# PSU.net
KiCad netlist of a schematic drawn in Altium Designer
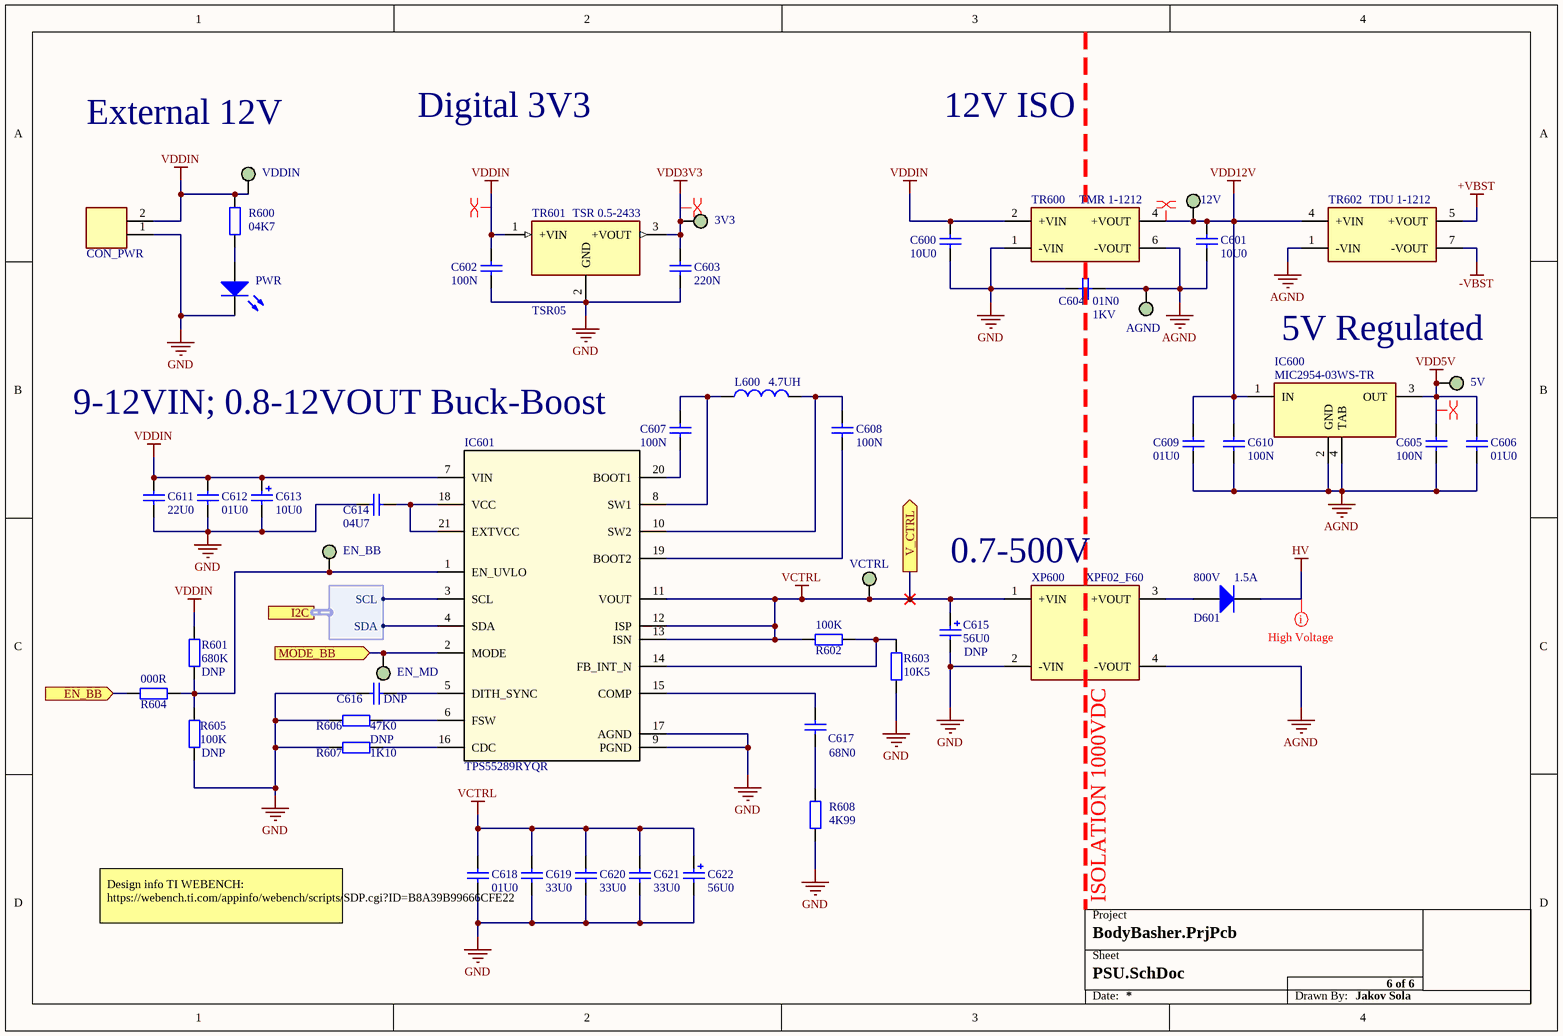
[diagram p0: PSU.SchDoc]

(export (version "E")
  (design (tool "Eeschema 10.0.6"))
  (components
    (comp (ref "3V3") (value "TP") (footprint "TP") (libsource (lib "Other_passive") (part "TP")))
    (comp (ref "5V") (value "TP") (footprint "TP") (libsource (lib "Other_passive") (part "TP")))
    (comp (ref "12V") (value "TP") (footprint "TP") (libsource (lib "Other_passive") (part "TP")))
    (comp (ref "AGND") (value "TP") (footprint "TP") (libsource (lib "Other_passive") (part "TP")))
    (comp (ref "C600")
      (value "Cap")
      (footprint "CAPC0603N")
      (fields
        (field (name "VALUE_4C") "10U0")
        (field (name "VOLTAGE") "25V")
        (field (name "TOLERANCE") "0.2")
      )
      (libsource (lib "Capacitors") (part "Cap"))
    )
    (comp (ref "C601")
      (value "Cap")
      (footprint "CAPC0603N")
      (fields
        (field (name "VALUE_4C") "10U0")
        (field (name "VOLTAGE") "25V")
        (field (name "TOLERANCE") "0.2")
      )
      (libsource (lib "Capacitors") (part "Cap"))
    )
    (comp (ref "C602")
      (value "Cap")
      (footprint "CAPC0603N")
      (fields
        (field (name "VALUE_4C") "100N")
        (field (name "VOLTAGE") "25V")
        (field (name "TOLERANCE") "0.1")
      )
      (libsource (lib "Capacitors") (part "Cap"))
    )
    (comp (ref "C603")
      (value "Cap")
      (footprint "CAPC0603N")
      (fields
        (field (name "VALUE_4C") "220N")
        (field (name "VOLTAGE") "10V")
        (field (name "TOLERANCE") "0.1")
      )
      (libsource (lib "Capacitors") (part "Cap"))
    )
    (comp (ref "C604")
      (value "Cap")
      (footprint "CAPC1206N")
      (fields
        (field (name "VALUE_4C") "01N0")
        (field (name "VOLTAGE") "1KV")
        (field (name "TOLERANCE") "0.1")
      )
      (libsource (lib "Capacitors") (part "Cap"))
    )
    (comp (ref "C605")
      (value "Cap")
      (footprint "CAPC0603N")
      (fields
        (field (name "VALUE_4C") "100N")
        (field (name "VOLTAGE") "25V")
        (field (name "TOLERANCE") "0.1")
      )
      (libsource (lib "Capacitors") (part "Cap"))
    )
    (comp (ref "C606")
      (value "Cap")
      (footprint "CAPC0603N")
      (fields
        (field (name "VALUE_4C") "01U0")
        (field (name "VOLTAGE") "16V")
        (field (name "TOLERANCE") "0.1")
      )
      (libsource (lib "Capacitors") (part "Cap"))
    )
    (comp (ref "C607")
      (value "Cap")
      (footprint "CAPC0603N")
      (fields
        (field (name "VALUE_4C") "100N")
        (field (name "VOLTAGE") "25V")
        (field (name "TOLERANCE") "0.1")
      )
      (libsource (lib "Capacitors") (part "Cap"))
    )
    (comp (ref "C608")
      (value "Cap")
      (footprint "CAPC0603N")
      (fields
        (field (name "VALUE_4C") "100N")
        (field (name "VOLTAGE") "25V")
        (field (name "TOLERANCE") "0.1")
      )
      (libsource (lib "Capacitors") (part "Cap"))
    )
    (comp (ref "C609")
      (value "Cap")
      (footprint "CAPC0603N")
      (fields
        (field (name "VALUE_4C") "01U0")
        (field (name "VOLTAGE") "16V")
        (field (name "TOLERANCE") "0.1")
      )
      (libsource (lib "Capacitors") (part "Cap"))
    )
    (comp (ref "C610")
      (value "Cap")
      (footprint "CAPC0603N")
      (fields
        (field (name "VALUE_4C") "100N")
        (field (name "VOLTAGE") "25V")
        (field (name "TOLERANCE") "0.1")
      )
      (libsource (lib "Capacitors") (part "Cap"))
    )
    (comp (ref "C611")
      (value "Cap")
      (footprint "CAPC1206N")
      (fields
        (field (name "VALUE_4C") "22U0")
        (field (name "VOLTAGE") "25V")
        (field (name "TOLERANCE") "0.1")
      )
      (libsource (lib "Capacitors") (part "Cap"))
    )
    (comp (ref "C612")
      (value "Cap")
      (footprint "CAPC0603N")
      (fields
        (field (name "VALUE_4C") "01U0")
        (field (name "VOLTAGE") "25V")
        (field (name "TOLERANCE") "0.1")
      )
      (libsource (lib "Capacitors") (part "Cap"))
    )
    (comp (ref "C613")
      (value "CapPol")
      (footprint "C")
      (fields
        (field (name "VALUE_4C") "10U0")
        (field (name "VOLTAGE") "25V")
        (field (name "TOLERANCE") "0.1")
      )
      (libsource (lib "Capacitors") (part "CapPol"))
    )
    (comp (ref "C614")
      (value "Cap")
      (footprint "CAPC0603N")
      (fields
        (field (name "VALUE_4C") "04U7")
        (field (name "VOLTAGE") "16V")
        (field (name "TOLERANCE") "0.1")
      )
      (libsource (lib "Capacitors") (part "Cap"))
    )
    (comp (ref "C615")
      (value "CapPol")
      (footprint "20SVPF56MX")
      (fields
        (field (name "POPULATE") "DNP")
        (field (name "VALUE_4C") "56U0")
        (field (name "VOLTAGE") "20V")
        (field (name "TOLERANCE") "0.2")
      )
      (libsource (lib "Capacitors") (part "CapPol"))
    )
    (comp (ref "C616")
      (value "Cap")
      (footprint "CAPC0603N")
      (fields (field (name "POPULATE") "DNP") (field (name "VOLTAGE") "25V") (field (name "TOLERANCE") "0.1"))
      (libsource (lib "Capacitors") (part "Cap"))
    )
    (comp (ref "C617")
      (value "Cap")
      (footprint "CAPC0603N")
      (fields
        (field (name "VALUE_4C") "68N0")
        (field (name "VOLTAGE") "10V")
        (field (name "TOLERANCE") "0.1")
      )
      (libsource (lib "Capacitors") (part "Cap"))
    )
    (comp (ref "C618")
      (value "Cap")
      (footprint "CAPC0603N")
      (fields
        (field (name "VALUE_4C") "01U0")
        (field (name "VOLTAGE") "25V")
        (field (name "TOLERANCE") "0.1")
      )
      (libsource (lib "Capacitors") (part "Cap"))
    )
    (comp (ref "C619")
      (value "Cap")
      (footprint "CAPC1206N")
      (fields
        (field (name "VALUE_4C") "33U0")
        (field (name "VOLTAGE") "25V")
        (field (name "TOLERANCE") "0.2")
      )
      (libsource (lib "Capacitors") (part "Cap"))
    )
    (comp (ref "C620")
      (value "Cap")
      (footprint "CAPC1206N")
      (fields
        (field (name "VALUE_4C") "33U0")
        (field (name "VOLTAGE") "25V")
        (field (name "TOLERANCE") "0.2")
      )
      (libsource (lib "Capacitors") (part "Cap"))
    )
    (comp (ref "C621")
      (value "Cap")
      (footprint "CAPC1206N")
      (fields
        (field (name "VALUE_4C") "33U0")
        (field (name "VOLTAGE") "25V")
        (field (name "TOLERANCE") "0.2")
      )
      (libsource (lib "Capacitors") (part "Cap"))
    )
    (comp (ref "C622")
      (value "CapPol")
      (footprint "20SVPF56MX")
      (fields
        (field (name "VALUE_4C") "56U0")
        (field (name "VOLTAGE") "20V")
        (field (name "TOLERANCE") "0.2")
      )
      (libsource (lib "Capacitors") (part "CapPol"))
    )
    (comp (ref "CON_PWR")
      (value "CON_2P")
      (footprint "1711725")
      (libsource (lib "Other_passive") (part "CON_2P"))
    )
    (comp (ref "D601")
      (value "Diode")
      (footprint "DIOSMB")
      (description "Default Diode")
      (fields (field (name "IF") "1.5A") (field (name "VR") "800V"))
      (libsource (lib "Diodes") (part "Diode"))
    )
    (comp (ref "EN_BB") (value "TP") (footprint "TP") (libsource (lib "Other_passive") (part "TP")))
    (comp (ref "EN_MD") (value "TP") (footprint "TP") (libsource (lib "Other_passive") (part "TP")))
    (comp (ref "IC600")
      (value "MIC2954-03WS-TR")
      (footprint "SOT230P700X180-4N")
      (fields (field (name "MANUFCODE") "MIC2954-03WS-TR"))
      (libsource (lib "Integrated_circuits") (part "MIC2954-03WS-TR"))
    )
    (comp (ref "IC601")
      (value "TPS55289RYQR")
      (footprint "RYQ0021A-MFG")
      (fields (field (name "MANUFCODE") "TPS55289RYQR"))
      (libsource (lib "Integrated_circuits") (part "TPS55289RYQR"))
    )
    (comp (ref "L600")
      (value "Inductor")
      (footprint "SRN80404R7Y")
      (fields (field (name "INDUCTANCE") "4.7UH"))
      (libsource (lib "Other_passive") (part "Inductor"))
    )
    (comp (ref "PWR") (value "LED") (footprint "LED0603_GREEN") (libsource (lib "Diodes") (part "LED")))
    (comp (ref "R600")
      (value "Res")
      (footprint "RESC0603N")
      (description "Resistor")
      (fields (field (name "VALUE_4C") "04K7") (field (name "POWER") "0.1W") (field (name "TOLERANCE") "5%"))
      (libsource (lib "Resistors") (part "Res"))
    )
    (comp (ref "R601")
      (value "Res")
      (footprint "RESC0603N")
      (description "Resistor")
      (fields
        (field (name "POPULATE") "DNP")
        (field (name "VALUE_4C") "680K")
        (field (name "POWER") "0.1W")
        (field (name "TOLERANCE") "1%")
      )
      (libsource (lib "Resistors") (part "Res"))
    )
    (comp (ref "R602")
      (value "Res")
      (footprint "RESC0603N")
      (description "Resistor")
      (fields
        (field (name "VALUE_4C") "100K")
        (field (name "POWER") "0.063W")
        (field (name "TOLERANCE") "1%")
      )
      (libsource (lib "") (part "Res_2"))
    )
    (comp (ref "R603")
      (value "Res")
      (footprint "RESC0603N")
      (description "Resistor")
      (fields
        (field (name "VALUE_4C") "10K5")
        (field (name "POWER") "0.063W")
        (field (name "TOLERANCE") "1%")
      )
      (libsource (lib "") (part "Res_3"))
    )
    (comp (ref "R604")
      (value "Res")
      (footprint "RESC0603N")
      (description "Resistor")
      (fields (field (name "VALUE_4C") "000R") (field (name "POWER") "0.1W") (field (name "TOLERANCE") "1%"))
      (libsource (lib "") (part "Res_2"))
    )
    (comp (ref "R605")
      (value "Res")
      (footprint "RESC0603N")
      (description "Resistor")
      (fields
        (field (name "POPULATE") "DNP")
        (field (name "VALUE_4C") "100K")
        (field (name "POWER") "0.063W")
        (field (name "TOLERANCE") "1%")
      )
      (libsource (lib "Resistors") (part "Res"))
    )
    (comp (ref "R606")
      (value "Res")
      (footprint "RESC0603N")
      (description "Resistor")
      (fields (field (name "VALUE_4C") "47K0") (field (name "POWER") "0.1W") (field (name "TOLERANCE") "1%"))
      (libsource (lib "") (part "Res_1"))
    )
    (comp (ref "R607")
      (value "Res")
      (footprint "RESC0603N")
      (description "Resistor")
      (fields
        (field (name "POPULATE") "DNP")
        (field (name "VALUE_4C") "1K10")
        (field (name "POWER") "0.1W")
        (field (name "TOLERANCE") "1%")
      )
      (libsource (lib "") (part "Res_2"))
    )
    (comp (ref "R608")
      (value "Res")
      (footprint "RESC0603N")
      (description "Resistor")
      (fields
        (field (name "VALUE_4C") "4K99")
        (field (name "POWER") "0.063W")
        (field (name "TOLERANCE") "1%")
      )
      (libsource (lib "Resistors") (part "Res"))
    )
    (comp (ref "TR600")
      (value "TMR1")
      (footprint "TMR1")
      (fields (field (name "MANUFCODE") "TMR 1-1212"))
      (libsource (lib "Integrated_circuits") (part "TMR1"))
    )
    (comp (ref "TR601")
      (value "TSR05")
      (footprint "TSR05")
      (fields (field (name "MANUFCODE") "TSR 0.5-2433"))
      (libsource (lib "Integrated_circuits") (part "TSR05"))
    )
    (comp (ref "TR602")
      (value "TDU1")
      (footprint "TDU1")
      (fields (field (name "MANUFCODE") "TDU 1-1212"))
      (libsource (lib "Integrated_circuits") (part "TDU1"))
    )
    (comp (ref "VCTRL") (value "TP") (footprint "TP") (libsource (lib "Other_passive") (part "TP")))
    (comp (ref "VDDIN") (value "TP") (footprint "TP") (libsource (lib "Other_passive") (part "TP")))
    (comp (ref "XP600")
      (value "XPF02_F60")
      (footprint "XPF02_F60")
      (libsource (lib "Integrated_circuits") (part "XPF02_F60"))
    )
  )
  (nets
    (net (code "2") (name "+VBST") (class "Default")
      (node (ref "TR602") (pin "5") (pinfunction "+VOUT_5") (pintype "power_in"))
    )
    (net (code "3") (name "-VBST") (class "Default")
      (node (ref "TR602") (pin "7") (pinfunction "-VOUT_7") (pintype "power_in"))
    )
    (net (code "4") (name "/EN_BB") (class "Default")
      (node (ref "R604") (pin "1") (pinfunction "1_1") (pintype "passive"))
    )
    (net (code "5") (name "/MODE_BB") (class "Default")
      (node (ref "EN_MD") (pin "TP") (pinfunction "TP_TP") (pintype "passive"))
      (node (ref "IC601") (pin "2") (pinfunction "MODE_2") (pintype "passive"))
    )
    (net (code "6") (name "/SCL") (class "Default")
      (node (ref "IC601") (pin "3") (pinfunction "SCL_3") (pintype "passive"))
    )
    (net (code "7") (name "/SDA") (class "Default")
      (node (ref "IC601") (pin "4") (pinfunction "SDA_4") (pintype "passive"))
    )
    (net (code "9") (name "AGND") (class "Default")
      (node (ref "AGND") (pin "TP") (pinfunction "TP_TP") (pintype "passive"))
      (node (ref "C601") (pin "1") (pinfunction "1_1") (pintype "passive"))
      (node (ref "C604") (pin "2") (pinfunction "2_2") (pintype "passive"))
      (node (ref "C605") (pin "1") (pinfunction "1_1") (pintype "passive"))
      (node (ref "C606") (pin "1") (pinfunction "1_1") (pintype "passive"))
      (node (ref "C609") (pin "1") (pinfunction "1_1") (pintype "passive"))
      (node (ref "C610") (pin "1") (pinfunction "1_1") (pintype "passive"))
      (node (ref "IC600") (pin "2") (pinfunction "GND_2") (pintype "passive"))
      (node (ref "IC600") (pin "4") (pinfunction "TAB_4") (pintype "passive"))
      (node (ref "TR600") (pin "6") (pinfunction "-VOUT_6") (pintype "power_in"))
      (node (ref "TR602") (pin "1") (pinfunction "-VIN_1") (pintype "power_in"))
      (node (ref "XP600") (pin "4") (pinfunction "-VOUT_4") (pintype "power_in"))
    )
    (net (code "10") (name "GND") (class "Default")
      (node (ref "C600") (pin "1") (pinfunction "1_1") (pintype "passive"))
      (node (ref "C602") (pin "1") (pinfunction "1_1") (pintype "passive"))
      (node (ref "C603") (pin "1") (pinfunction "1_1") (pintype "passive"))
      (node (ref "C604") (pin "1") (pinfunction "1_1") (pintype "passive"))
      (node (ref "C611") (pin "1") (pinfunction "1_1") (pintype "passive"))
      (node (ref "C612") (pin "1") (pinfunction "1_1") (pintype "passive"))
      (node (ref "C613") (pin "2") (pinfunction "2_2") (pintype "passive"))
      (node (ref "C614") (pin "1") (pinfunction "1_1") (pintype "passive"))
      (node (ref "C615") (pin "2") (pinfunction "2_2") (pintype "passive"))
      (node (ref "C616") (pin "2") (pinfunction "2_2") (pintype "passive"))
      (node (ref "C618") (pin "1") (pinfunction "1_1") (pintype "passive"))
      (node (ref "C619") (pin "1") (pinfunction "1_1") (pintype "passive"))
      (node (ref "C620") (pin "1") (pinfunction "1_1") (pintype "passive"))
      (node (ref "C621") (pin "1") (pinfunction "1_1") (pintype "passive"))
      (node (ref "C622") (pin "2") (pinfunction "2_2") (pintype "passive"))
      (node (ref "CON_PWR") (pin "1") (pinfunction "1_1") (pintype "passive"))
      (node (ref "IC601") (pin "17") (pinfunction "AGND_17") (pintype "passive"))
      (node (ref "IC601") (pin "9") (pinfunction "PGND_9") (pintype "passive"))
      (node (ref "PWR") (pin "2") (pinfunction "K_2") (pintype "passive"))
      (node (ref "R603") (pin "2") (pinfunction "2_2") (pintype "passive"))
      (node (ref "R605") (pin "1") (pinfunction "1_1") (pintype "passive"))
      (node (ref "R606") (pin "2") (pinfunction "2_2") (pintype "passive"))
      (node (ref "R607") (pin "1") (pinfunction "1_1") (pintype "passive"))
      (node (ref "R608") (pin "1") (pinfunction "1_1") (pintype "passive"))
      (node (ref "TR600") (pin "1") (pinfunction "-VIN_1") (pintype "power_in"))
      (node (ref "TR601") (pin "2") (pinfunction "GND_2") (pintype "power_in"))
      (node (ref "XP600") (pin "2") (pinfunction "-VIN_2") (pintype "power_in"))
    )
    (net (code "11") (name "HV") (class "Default")
      (node (ref "D601") (pin "2") (pinfunction "K_2") (pintype "passive"))
    )
    (net (code "12") (name "Net-(C617-Pad1)") (class "Default")
      (node (ref "C617") (pin "1") (pinfunction "1_1") (pintype "passive"))
      (node (ref "R608") (pin "2") (pinfunction "2_2") (pintype "passive"))
    )
    (net (code "13") (name "Net-(D601-A)") (class "Default")
      (node (ref "D601") (pin "1") (pinfunction "A_1") (pintype "passive"))
      (node (ref "XP600") (pin "3") (pinfunction "+VOUT_3") (pintype "power_in"))
    )
    (net (code "14") (name "Net-(IC601-BOOT1)") (class "Default")
      (node (ref "C607") (pin "1") (pinfunction "1_1") (pintype "passive"))
      (node (ref "IC601") (pin "20") (pinfunction "BOOT1_20") (pintype "passive"))
    )
    (net (code "15") (name "Net-(IC601-BOOT2)") (class "Default")
      (node (ref "C608") (pin "1") (pinfunction "1_1") (pintype "passive"))
      (node (ref "IC601") (pin "19") (pinfunction "BOOT2_19") (pintype "passive"))
    )
    (net (code "16") (name "Net-(IC601-CDC)") (class "Default")
      (node (ref "IC601") (pin "16") (pinfunction "CDC_16") (pintype "passive"))
      (node (ref "R607") (pin "2") (pinfunction "2_2") (pintype "passive"))
    )
    (net (code "17") (name "Net-(IC601-COMP)") (class "Default")
      (node (ref "C617") (pin "2") (pinfunction "2_2") (pintype "passive"))
      (node (ref "IC601") (pin "15") (pinfunction "COMP_15") (pintype "passive"))
    )
    (net (code "18") (name "Net-(IC601-DITH_SYNC)") (class "Default")
      (node (ref "C616") (pin "1") (pinfunction "1_1") (pintype "passive"))
      (node (ref "IC601") (pin "5") (pinfunction "DITH_SYNC_5") (pintype "passive"))
    )
    (net (code "19") (name "Net-(IC601-EN_UVLO)") (class "Default")
      (node (ref "EN_BB") (pin "TP") (pinfunction "TP_TP") (pintype "passive"))
      (node (ref "IC601") (pin "1") (pinfunction "EN_UVLO_1") (pintype "passive"))
      (node (ref "R601") (pin "1") (pinfunction "1_1") (pintype "passive"))
      (node (ref "R604") (pin "2") (pinfunction "2_2") (pintype "passive"))
      (node (ref "R605") (pin "2") (pinfunction "2_2") (pintype "passive"))
    )
    (net (code "20") (name "Net-(IC601-EXTVCC)") (class "Default")
      (node (ref "C614") (pin "2") (pinfunction "2_2") (pintype "passive"))
      (node (ref "IC601") (pin "18") (pinfunction "VCC_18") (pintype "passive"))
      (node (ref "IC601") (pin "21") (pinfunction "EXTVCC_21") (pintype "passive"))
    )
    (net (code "21") (name "Net-(IC601-FB_INT_N)") (class "Default")
      (node (ref "IC601") (pin "14") (pinfunction "FB_INT_N_14") (pintype "passive"))
      (node (ref "R602") (pin "2") (pinfunction "2_2") (pintype "passive"))
      (node (ref "R603") (pin "1") (pinfunction "1_1") (pintype "passive"))
    )
    (net (code "22") (name "Net-(IC601-FSW)") (class "Default")
      (node (ref "IC601") (pin "6") (pinfunction "FSW_6") (pintype "passive"))
      (node (ref "R606") (pin "1") (pinfunction "1_1") (pintype "passive"))
    )
    (net (code "23") (name "Net-(IC601-SW1)") (class "Default")
      (node (ref "C607") (pin "2") (pinfunction "2_2") (pintype "passive"))
      (node (ref "IC601") (pin "8") (pinfunction "SW1_8") (pintype "passive"))
      (node (ref "L600") (pin "1") (pinfunction "1_1") (pintype "passive"))
    )
    (net (code "24") (name "Net-(IC601-SW2)") (class "Default")
      (node (ref "C608") (pin "2") (pinfunction "2_2") (pintype "passive"))
      (node (ref "IC601") (pin "10") (pinfunction "SW2_10") (pintype "passive"))
      (node (ref "L600") (pin "2") (pinfunction "2_2") (pintype "passive"))
    )
    (net (code "25") (name "Net-(PWR-A)") (class "Default")
      (node (ref "PWR") (pin "1") (pinfunction "A_1") (pintype "passive"))
      (node (ref "R600") (pin "1") (pinfunction "1_1") (pintype "passive"))
    )
    (net (code "26") (name "VCTRL") (class "Default")
      (node (ref "C615") (pin "1") (pinfunction "1_1") (pintype "passive"))
      (node (ref "C618") (pin "2") (pinfunction "2_2") (pintype "passive"))
      (node (ref "C619") (pin "2") (pinfunction "2_2") (pintype "passive"))
      (node (ref "C620") (pin "2") (pinfunction "2_2") (pintype "passive"))
      (node (ref "C621") (pin "2") (pinfunction "2_2") (pintype "passive"))
      (node (ref "C622") (pin "1") (pinfunction "1_1") (pintype "passive"))
      (node (ref "IC601") (pin "11") (pinfunction "VOUT_11") (pintype "passive"))
      (node (ref "IC601") (pin "12") (pinfunction "ISP_12") (pintype "passive"))
      (node (ref "IC601") (pin "13") (pinfunction "ISN_13") (pintype "passive"))
      (node (ref "R602") (pin "1") (pinfunction "1_1") (pintype "passive"))
      (node (ref "VCTRL") (pin "TP") (pinfunction "TP_TP") (pintype "passive"))
      (node (ref "XP600") (pin "1") (pinfunction "+VIN_1") (pintype "power_in"))
    )
    (net (code "27") (name "VDD3V3") (class "Default")
      (node (ref "3V3") (pin "TP") (pinfunction "TP_TP") (pintype "passive"))
      (node (ref "C603") (pin "2") (pinfunction "2_2") (pintype "passive"))
      (node (ref "TR601") (pin "3") (pinfunction "+VOUT_3") (pintype "output"))
    )
    (net (code "28") (name "VDD5V") (class "Default")
      (node (ref "5V") (pin "TP") (pinfunction "TP_TP") (pintype "passive"))
      (node (ref "C605") (pin "2") (pinfunction "2_2") (pintype "passive"))
      (node (ref "C606") (pin "2") (pinfunction "2_2") (pintype "passive"))
      (node (ref "IC600") (pin "3") (pinfunction "OUT_3") (pintype "passive"))
    )
    (net (code "29") (name "VDD12V") (class "Default")
      (node (ref "12V") (pin "TP") (pinfunction "TP_TP") (pintype "passive"))
      (node (ref "C601") (pin "2") (pinfunction "2_2") (pintype "passive"))
      (node (ref "C609") (pin "2") (pinfunction "2_2") (pintype "passive"))
      (node (ref "C610") (pin "2") (pinfunction "2_2") (pintype "passive"))
      (node (ref "IC600") (pin "1") (pinfunction "IN_1") (pintype "passive"))
      (node (ref "TR600") (pin "4") (pinfunction "+VOUT_4") (pintype "power_in"))
      (node (ref "TR602") (pin "4") (pinfunction "+VIN_4") (pintype "power_in"))
    )
    (net (code "30") (name "VDDIN") (class "Default")
      (node (ref "C600") (pin "2") (pinfunction "2_2") (pintype "passive"))
      (node (ref "C602") (pin "2") (pinfunction "2_2") (pintype "passive"))
      (node (ref "C611") (pin "2") (pinfunction "2_2") (pintype "passive"))
      (node (ref "C612") (pin "2") (pinfunction "2_2") (pintype "passive"))
      (node (ref "C613") (pin "1") (pinfunction "1_1") (pintype "passive"))
      (node (ref "CON_PWR") (pin "2") (pinfunction "2_2") (pintype "passive"))
      (node (ref "IC601") (pin "7") (pinfunction "VIN_7") (pintype "passive"))
      (node (ref "R600") (pin "2") (pinfunction "2_2") (pintype "passive"))
      (node (ref "R601") (pin "2") (pinfunction "2_2") (pintype "passive"))
      (node (ref "TR600") (pin "2") (pinfunction "+VIN_2") (pintype "power_in"))
      (node (ref "TR601") (pin "1") (pinfunction "+VIN_1") (pintype "input"))
      (node (ref "VDDIN") (pin "TP") (pinfunction "TP_TP") (pintype "passive"))
    )
  )
)
